# TYPK.net
KiCad netlist of a schematic drawn in Altium Designer
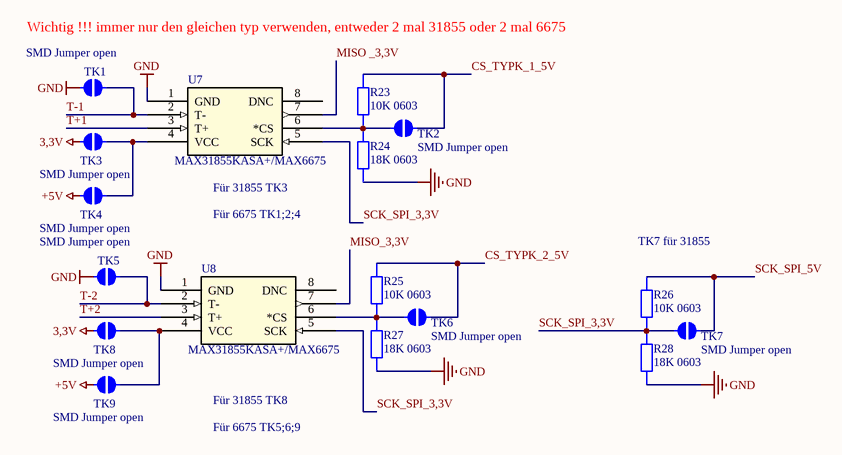
[diagram p0: TYPK.SchDoc]

(export (version "E")
  (design (tool "Eeschema 10.0.6"))
  (components
    (comp (ref "R23")
      (value "10K 0603")
      (footprint "STACKPOLE CSR0603")
      (description "Resistor with multiple footprints")
      (fields (field (name "Comment") "SMD Resistor"))
      (libsource (lib "Standardbauteile") (part "SMD Resistor"))
    )
    (comp (ref "R24")
      (value "18K 0603")
      (footprint "STACKPOLE CSR0603")
      (description "Resistor with multiple footprints")
      (fields (field (name "Comment") "SMD Resistor"))
      (libsource (lib "Standardbauteile") (part "SMD Resistor"))
    )
    (comp (ref "R25")
      (value "10K 0603")
      (footprint "STACKPOLE CSR0603")
      (description "Resistor with multiple footprints")
      (fields (field (name "Comment") "SMD Resistor"))
      (libsource (lib "Standardbauteile") (part "SMD Resistor"))
    )
    (comp (ref "R26")
      (value "10K 0603")
      (footprint "STACKPOLE CSR0603")
      (description "Resistor with multiple footprints")
      (fields (field (name "Comment") "SMD Resistor"))
      (libsource (lib "Standardbauteile") (part "SMD Resistor"))
    )
    (comp (ref "R27")
      (value "18K 0603")
      (footprint "STACKPOLE CSR0603")
      (description "Resistor with multiple footprints")
      (fields (field (name "Comment") "SMD Resistor"))
      (libsource (lib "Standardbauteile") (part "SMD Resistor"))
    )
    (comp (ref "R28")
      (value "18K 0603")
      (footprint "STACKPOLE CSR0603")
      (description "Resistor with multiple footprints")
      (fields (field (name "Comment") "SMD Resistor"))
      (libsource (lib "Standardbauteile") (part "SMD Resistor"))
    )
    (comp (ref "TK1")
      (value "SMD Jumper open")
      (footprint "SMD-JUMPER-OPEN")
      (libsource (lib "Standardbauteile") (part "SMD Jumper open"))
    )
    (comp (ref "TK2")
      (value "SMD Jumper open")
      (footprint "SMD-JUMPER-OPEN")
      (libsource (lib "Standardbauteile") (part "SMD Jumper open"))
    )
    (comp (ref "TK3")
      (value "SMD Jumper open")
      (footprint "SMD-JUMPER-OPEN")
      (libsource (lib "Standardbauteile") (part "SMD Jumper open"))
    )
    (comp (ref "TK4")
      (value "SMD Jumper open")
      (footprint "SMD-JUMPER-OPEN")
      (libsource (lib "Standardbauteile") (part "SMD Jumper open"))
    )
    (comp (ref "TK5")
      (value "SMD Jumper open")
      (footprint "SMD-JUMPER-OPEN")
      (libsource (lib "Standardbauteile") (part "SMD Jumper open"))
    )
    (comp (ref "TK6")
      (value "SMD Jumper open")
      (footprint "SMD-JUMPER-OPEN")
      (libsource (lib "Standardbauteile") (part "SMD Jumper open"))
    )
    (comp (ref "TK7")
      (value "SMD Jumper open")
      (footprint "SMD-JUMPER-OPEN")
      (libsource (lib "Standardbauteile") (part "SMD Jumper open"))
    )
    (comp (ref "TK8")
      (value "SMD Jumper open")
      (footprint "SMD-JUMPER-OPEN")
      (libsource (lib "Standardbauteile") (part "SMD Jumper open"))
    )
    (comp (ref "TK9")
      (value "SMD Jumper open")
      (footprint "SMD-JUMPER-OPEN")
      (libsource (lib "Standardbauteile") (part "SMD Jumper open"))
    )
    (comp (ref "U7")
      (value "MAX31855KASA+/MAX6675")
      (footprint "SOIC8")
      (description "No Description Available")
      (fields
        (field (name "MANUFACTURER_PART_NUMBER") "MAX31855KASA+")
        (field (name "COPYRIGHT") "Copyright (C) 2018 Accelerated Designs. All rights reserved")
      )
      (libsource (lib "Eric") (part "MAX31855KASA+"))
    )
    (comp (ref "U8")
      (value "MAX31855KASA+/MAX6675")
      (footprint "SOIC8")
      (description "No Description Available")
      (fields
        (field (name "MANUFACTURER_PART_NUMBER") "MAX31855KASA+")
        (field (name "COPYRIGHT") "Copyright (C) 2018 Accelerated Designs. All rights reserved")
      )
      (libsource (lib "Eric") (part "MAX31855KASA+"))
    )
  )
  (nets
    (net (code "1") (name "+5V") (class "Default")
      (node (ref "TK4") (pin "1") (pinfunction "1_1") (pintype "passive"))
      (node (ref "TK9") (pin "1") (pinfunction "1_1") (pintype "passive"))
    )
    (net (code "2") (name "/CS_TYPK_1_5V") (class "Default")
      (node (ref "R23") (pin "2") (pinfunction "2_2") (pintype "passive"))
      (node (ref "TK2") (pin "2") (pinfunction "2_2") (pintype "passive"))
    )
    (net (code "3") (name "/CS_TYPK_2_5V") (class "Default")
      (node (ref "R25") (pin "2") (pinfunction "2_2") (pintype "passive"))
      (node (ref "TK6") (pin "2") (pinfunction "2_2") (pintype "passive"))
    )
    (net (code "4") (name "/MISO _3,3V") (class "Default")
      (node (ref "U7") (pin "7") (pinfunction "SO_7") (pintype "output"))
    )
    (net (code "5") (name "/MISO_3,3V") (class "Default")
      (node (ref "U8") (pin "7") (pinfunction "SO_7") (pintype "output"))
    )
    (net (code "6") (name "/SCK_SPI_3,3V") (class "Default")
      (node (ref "R26") (pin "1") (pinfunction "1_1") (pintype "passive"))
      (node (ref "R28") (pin "2") (pinfunction "2_2") (pintype "passive"))
      (node (ref "TK7") (pin "1") (pinfunction "1_1") (pintype "passive"))
      (node (ref "U7") (pin "5") (pinfunction "SCK_5") (pintype "input"))
      (node (ref "U8") (pin "5") (pinfunction "SCK_5") (pintype "input"))
    )
    (net (code "7") (name "/SCK_SPI_5V") (class "Default")
      (node (ref "R26") (pin "2") (pinfunction "2_2") (pintype "passive"))
      (node (ref "TK7") (pin "2") (pinfunction "2_2") (pintype "passive"))
    )
    (net (code "8") (name "/T+1") (class "Default")
      (node (ref "U7") (pin "3") (pinfunction "T+_3") (pintype "input"))
    )
    (net (code "9") (name "/T+2") (class "Default")
      (node (ref "U8") (pin "3") (pinfunction "T+_3") (pintype "input"))
    )
    (net (code "10") (name "/T-1") (class "Default")
      (node (ref "TK1") (pin "2") (pinfunction "2_2") (pintype "passive"))
      (node (ref "U7") (pin "2") (pinfunction "T-_2") (pintype "input"))
    )
    (net (code "11") (name "/T-2") (class "Default")
      (node (ref "TK5") (pin "2") (pinfunction "2_2") (pintype "passive"))
      (node (ref "U8") (pin "2") (pinfunction "T-_2") (pintype "input"))
    )
    (net (code "12") (name "3,3V") (class "Default")
      (node (ref "TK3") (pin "1") (pinfunction "1_1") (pintype "passive"))
      (node (ref "TK8") (pin "1") (pinfunction "1_1") (pintype "passive"))
    )
    (net (code "13") (name "GND") (class "Default")
      (node (ref "R24") (pin "1") (pinfunction "1_1") (pintype "passive"))
      (node (ref "R27") (pin "1") (pinfunction "1_1") (pintype "passive"))
      (node (ref "R28") (pin "1") (pinfunction "1_1") (pintype "passive"))
      (node (ref "TK1") (pin "1") (pinfunction "1_1") (pintype "passive"))
      (node (ref "TK5") (pin "1") (pinfunction "1_1") (pintype "passive"))
      (node (ref "U7") (pin "1") (pinfunction "GND_1") (pintype "power_in"))
      (node (ref "U8") (pin "1") (pinfunction "GND_1") (pintype "power_in"))
    )
    (net (code "14") (name "Net-(U7-*CS)") (class "Default")
      (node (ref "R23") (pin "1") (pinfunction "1_1") (pintype "passive"))
      (node (ref "R24") (pin "2") (pinfunction "2_2") (pintype "passive"))
      (node (ref "TK2") (pin "1") (pinfunction "1_1") (pintype "passive"))
      (node (ref "U7") (pin "6") (pinfunction "*CS_6") (pintype "passive"))
    )
    (net (code "15") (name "Net-(U7-VCC)") (class "Default")
      (node (ref "TK3") (pin "2") (pinfunction "2_2") (pintype "passive"))
      (node (ref "TK4") (pin "2") (pinfunction "2_2") (pintype "passive"))
      (node (ref "U7") (pin "4") (pinfunction "VCC_4") (pintype "power_in"))
    )
    (net (code "16") (name "Net-(U8-*CS)") (class "Default")
      (node (ref "R25") (pin "1") (pinfunction "1_1") (pintype "passive"))
      (node (ref "R27") (pin "2") (pinfunction "2_2") (pintype "passive"))
      (node (ref "TK6") (pin "1") (pinfunction "1_1") (pintype "passive"))
      (node (ref "U8") (pin "6") (pinfunction "*CS_6") (pintype "passive"))
    )
    (net (code "17") (name "Net-(U8-VCC)") (class "Default")
      (node (ref "TK8") (pin "2") (pinfunction "2_2") (pintype "passive"))
      (node (ref "TK9") (pin "2") (pinfunction "2_2") (pintype "passive"))
      (node (ref "U8") (pin "4") (pinfunction "VCC_4") (pintype "power_in"))
    )
    (net (code "18") (name "unconnected-(U7-DNC-Pad8)") (class "Default")
      (node (ref "U7") (pin "8") (pinfunction "DNC_8") (pintype "passive"))
    )
    (net (code "19") (name "unconnected-(U8-DNC-Pad8)") (class "Default")
      (node (ref "U8") (pin "8") (pinfunction "DNC_8") (pintype "passive"))
    )
  )
)
